# vers1_0.net
KiCad netlist of a schematic drawn in Altium Designer
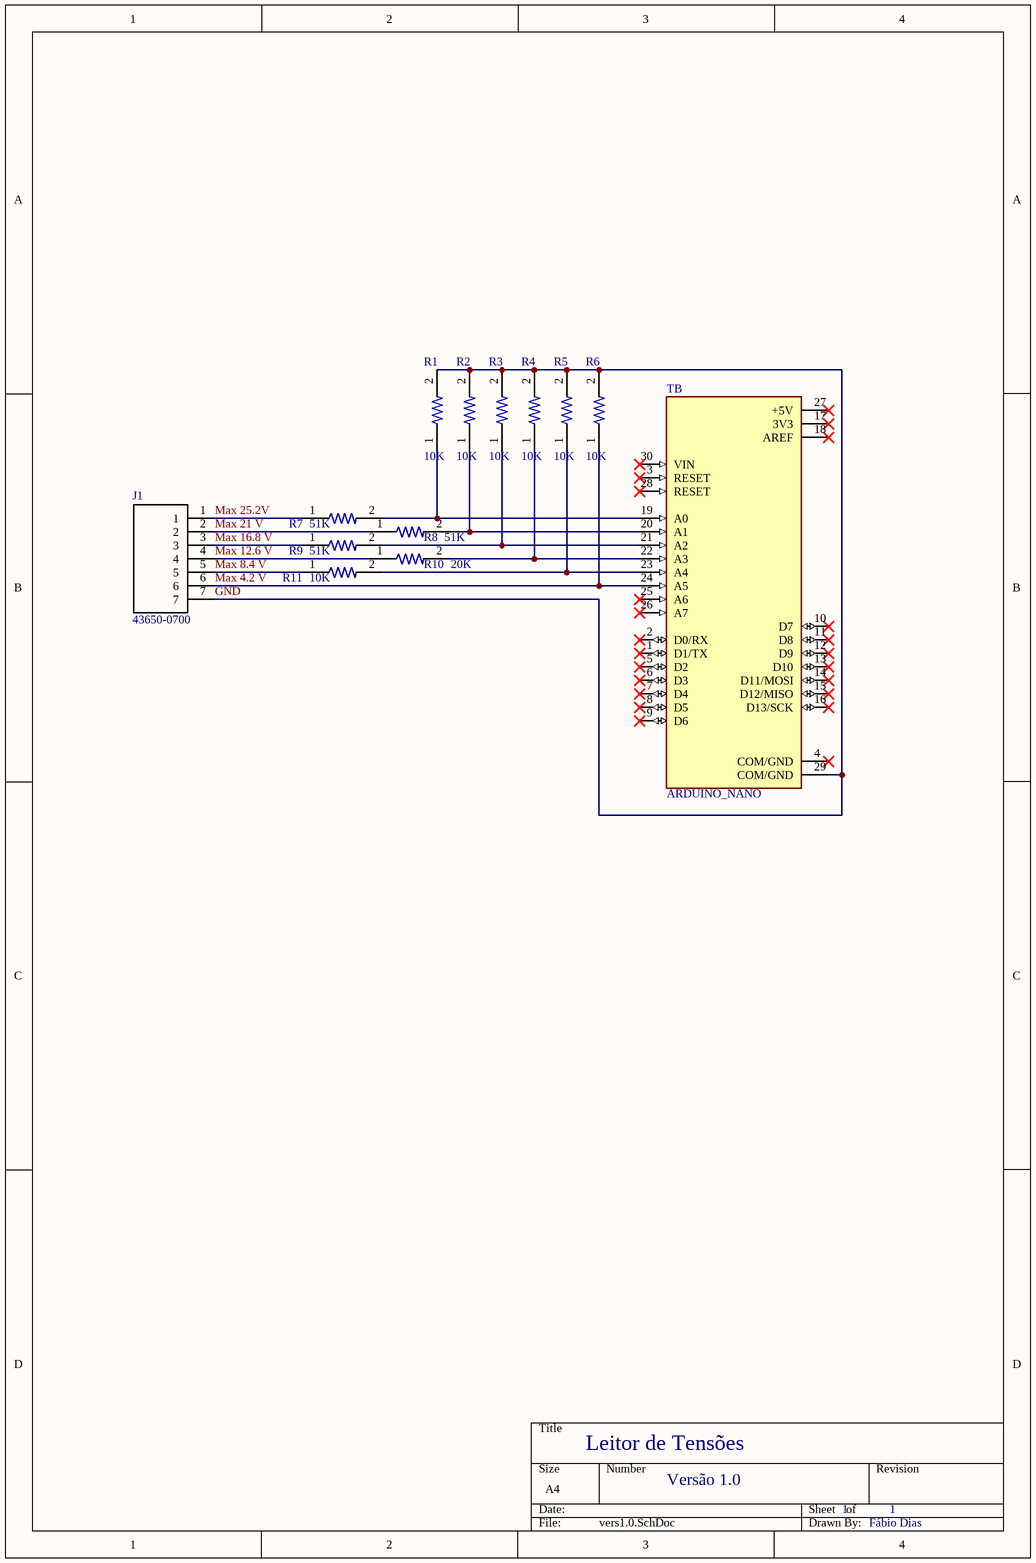
[diagram p0: vers1.0.SchDoc]

(export (version "E")
  (design (tool "Eeschema 10.0.6"))
  (components
    (comp (ref "J1")
      (value "43650-0700")
      (footprint "SamacSys:43650-07YY_R")
      (description "Connector")
      (fields (field (name "MOUSER PART NUMBER") "538-43650-0700"))
      (libsource (lib "*") (part "43650-0700"))
    )
    (comp (ref "R1")
      (value "10K")
      (footprint "R 0201")
      (description "Resistencia")
      (libsource (lib "MotoLibrary") (part "Resistencia"))
    )
    (comp (ref "R2")
      (value "10K")
      (footprint "R 0201")
      (description "Resistencia")
      (libsource (lib "MotoLibrary") (part "Resistencia"))
    )
    (comp (ref "R3")
      (value "10K")
      (footprint "R 0201")
      (description "Resistencia")
      (libsource (lib "MotoLibrary") (part "Resistencia"))
    )
    (comp (ref "R4")
      (value "10K")
      (footprint "R 0201")
      (description "Resistencia")
      (libsource (lib "MotoLibrary") (part "Resistencia"))
    )
    (comp (ref "R5")
      (value "10K")
      (footprint "R 0201")
      (description "Resistencia")
      (libsource (lib "MotoLibrary") (part "Resistencia"))
    )
    (comp (ref "R6")
      (value "10K")
      (footprint "R 0201")
      (description "Resistencia")
      (libsource (lib "MotoLibrary") (part "Resistencia"))
    )
    (comp (ref "R7")
      (value "51K")
      (footprint "R 0201")
      (description "Resistencia")
      (libsource (lib "MotoLibrary") (part "Resistencia"))
    )
    (comp (ref "R8")
      (value "51K")
      (footprint "R 0201")
      (description "Resistencia")
      (libsource (lib "MotoLibrary") (part "Resistencia"))
    )
    (comp (ref "R9")
      (value "51K")
      (footprint "R 0201")
      (description "Resistencia")
      (libsource (lib "MotoLibrary") (part "Resistencia"))
    )
    (comp (ref "R10")
      (value "20K")
      (footprint "R 0201")
      (description "Resistencia")
      (libsource (lib "MotoLibrary") (part "Resistencia"))
    )
    (comp (ref "R11")
      (value "10K")
      (footprint "R 0201")
      (description "Resistencia")
      (libsource (lib "MotoLibrary") (part "Resistencia"))
    )
    (comp (ref "TB")
      (value "ARDUINO_NANO")
      (footprint "SHIELD_ARDUINO_NANO")
      (description "ATSAMD21G18A Arduino Nano 33 IoT SAM D ARMÂ® CortexÂ®-M0+ MCU 32-Bit Embedded Evaluation Board")
      (fields (field (name "MP") "ARDUINO NANO") (field (name "MF") "Arduino"))
      (libsource (lib "ARDUINO_NANO") (part "ARDUINO_NANO"))
    )
  )
  (nets
    (net (code "1") (name "/GND") (class "Default")
      (node (ref "J1") (pin "7") (pinfunction "7_7") (pintype "passive"))
      (node (ref "R1") (pin "2") (pinfunction "2_2") (pintype "passive"))
      (node (ref "R2") (pin "2") (pinfunction "2_2") (pintype "passive"))
      (node (ref "R3") (pin "2") (pinfunction "2_2") (pintype "passive"))
      (node (ref "R4") (pin "2") (pinfunction "2_2") (pintype "passive"))
      (node (ref "R5") (pin "2") (pinfunction "2_2") (pintype "passive"))
      (node (ref "R6") (pin "2") (pinfunction "2_2") (pintype "passive"))
      (node (ref "TB") (pin "29") (pinfunction "COM/GND_29") (pintype "power_in"))
    )
    (net (code "2") (name "/Max 4.2 V") (class "Default")
      (node (ref "J1") (pin "6") (pinfunction "6_6") (pintype "passive"))
      (node (ref "R6") (pin "1") (pinfunction "1_1") (pintype "passive"))
      (node (ref "TB") (pin "24") (pinfunction "A5_24") (pintype "input"))
    )
    (net (code "3") (name "/Max 8.4 V") (class "Default")
      (node (ref "J1") (pin "5") (pinfunction "5_5") (pintype "passive"))
      (node (ref "R11") (pin "1") (pinfunction "1_1") (pintype "passive"))
    )
    (net (code "4") (name "/Max 12.6 V") (class "Default")
      (node (ref "J1") (pin "4") (pinfunction "4_4") (pintype "passive"))
      (node (ref "R10") (pin "1") (pinfunction "1_1") (pintype "passive"))
    )
    (net (code "5") (name "/Max 16.8 V") (class "Default")
      (node (ref "J1") (pin "3") (pinfunction "3_3") (pintype "passive"))
      (node (ref "R9") (pin "1") (pinfunction "1_1") (pintype "passive"))
    )
    (net (code "6") (name "/Max 21 V") (class "Default")
      (node (ref "J1") (pin "2") (pinfunction "2_2") (pintype "passive"))
      (node (ref "R8") (pin "1") (pinfunction "1_1") (pintype "passive"))
    )
    (net (code "7") (name "/Max 25.2V") (class "Default")
      (node (ref "J1") (pin "1") (pinfunction "1_1") (pintype "passive"))
      (node (ref "R7") (pin "1") (pinfunction "1_1") (pintype "passive"))
    )
    (net (code "8") (name "Net-(TB-A0)") (class "Default")
      (node (ref "R1") (pin "1") (pinfunction "1_1") (pintype "passive"))
      (node (ref "R7") (pin "2") (pinfunction "2_2") (pintype "passive"))
      (node (ref "TB") (pin "19") (pinfunction "A0_19") (pintype "input"))
    )
    (net (code "9") (name "Net-(TB-A1)") (class "Default")
      (node (ref "R2") (pin "1") (pinfunction "1_1") (pintype "passive"))
      (node (ref "R8") (pin "2") (pinfunction "2_2") (pintype "passive"))
      (node (ref "TB") (pin "20") (pinfunction "A1_20") (pintype "input"))
    )
    (net (code "10") (name "Net-(TB-A2)") (class "Default")
      (node (ref "R3") (pin "1") (pinfunction "1_1") (pintype "passive"))
      (node (ref "R9") (pin "2") (pinfunction "2_2") (pintype "passive"))
      (node (ref "TB") (pin "21") (pinfunction "A2_21") (pintype "input"))
    )
    (net (code "11") (name "Net-(TB-A3)") (class "Default")
      (node (ref "R10") (pin "2") (pinfunction "2_2") (pintype "passive"))
      (node (ref "R4") (pin "1") (pinfunction "1_1") (pintype "passive"))
      (node (ref "TB") (pin "22") (pinfunction "A3_22") (pintype "input"))
    )
    (net (code "12") (name "Net-(TB-A4)") (class "Default")
      (node (ref "R11") (pin "2") (pinfunction "2_2") (pintype "passive"))
      (node (ref "R5") (pin "1") (pinfunction "1_1") (pintype "passive"))
      (node (ref "TB") (pin "23") (pinfunction "A4_23") (pintype "input"))
    )
    (net (code "13") (name "unconnected-(TB-+5V-Pad27)") (class "Default")
      (node (ref "TB") (pin "27") (pinfunction "+5V_27") (pintype "power_in+no_connect"))
    )
    (net (code "14") (name "unconnected-(TB-3V3-Pad17)") (class "Default")
      (node (ref "TB") (pin "17") (pinfunction "3V3_17") (pintype "power_in+no_connect"))
    )
    (net (code "15") (name "unconnected-(TB-A6-Pad25)") (class "Default")
      (node (ref "TB") (pin "25") (pinfunction "A6_25") (pintype "input+no_connect"))
    )
    (net (code "16") (name "unconnected-(TB-A7-Pad26)") (class "Default")
      (node (ref "TB") (pin "26") (pinfunction "A7_26") (pintype "input+no_connect"))
    )
    (net (code "17") (name "unconnected-(TB-AREF-Pad18)") (class "Default")
      (node (ref "TB") (pin "18") (pinfunction "AREF_18") (pintype "power_in+no_connect"))
    )
    (net (code "18") (name "unconnected-(TB-COM{slash}GND-Pad4)") (class "Default")
      (node (ref "TB") (pin "4") (pinfunction "COM/GND_4") (pintype "power_in+no_connect"))
    )
    (net (code "19") (name "unconnected-(TB-D0{slash}RX-Pad2)") (class "Default")
      (node (ref "TB") (pin "2") (pinfunction "D0/RX_2") (pintype "bidirectional+no_connect"))
    )
    (net (code "20") (name "unconnected-(TB-D1{slash}TX-Pad1)") (class "Default")
      (node (ref "TB") (pin "1") (pinfunction "D1/TX_1") (pintype "bidirectional+no_connect"))
    )
    (net (code "21") (name "unconnected-(TB-D2-Pad5)") (class "Default")
      (node (ref "TB") (pin "5") (pinfunction "D2_5") (pintype "bidirectional+no_connect"))
    )
    (net (code "22") (name "unconnected-(TB-D3-Pad6)") (class "Default")
      (node (ref "TB") (pin "6") (pinfunction "D3_6") (pintype "bidirectional+no_connect"))
    )
    (net (code "23") (name "unconnected-(TB-D4-Pad7)") (class "Default")
      (node (ref "TB") (pin "7") (pinfunction "D4_7") (pintype "bidirectional+no_connect"))
    )
    (net (code "24") (name "unconnected-(TB-D5-Pad8)") (class "Default")
      (node (ref "TB") (pin "8") (pinfunction "D5_8") (pintype "bidirectional+no_connect"))
    )
    (net (code "25") (name "unconnected-(TB-D6-Pad9)") (class "Default")
      (node (ref "TB") (pin "9") (pinfunction "D6_9") (pintype "bidirectional+no_connect"))
    )
    (net (code "26") (name "unconnected-(TB-D7-Pad10)") (class "Default")
      (node (ref "TB") (pin "10") (pinfunction "D7_10") (pintype "bidirectional+no_connect"))
    )
    (net (code "27") (name "unconnected-(TB-D8-Pad11)") (class "Default")
      (node (ref "TB") (pin "11") (pinfunction "D8_11") (pintype "bidirectional+no_connect"))
    )
    (net (code "28") (name "unconnected-(TB-D9-Pad12)") (class "Default")
      (node (ref "TB") (pin "12") (pinfunction "D9_12") (pintype "bidirectional+no_connect"))
    )
    (net (code "29") (name "unconnected-(TB-D10-Pad13)") (class "Default")
      (node (ref "TB") (pin "13") (pinfunction "D10_13") (pintype "bidirectional+no_connect"))
    )
    (net (code "30") (name "unconnected-(TB-D11{slash}MOSI-Pad14)") (class "Default")
      (node (ref "TB") (pin "14") (pinfunction "D11/MOSI_14") (pintype "bidirectional+no_connect"))
    )
    (net (code "31") (name "unconnected-(TB-D12{slash}MISO-Pad15)") (class "Default")
      (node (ref "TB") (pin "15") (pinfunction "D12/MISO_15") (pintype "bidirectional+no_connect"))
    )
    (net (code "32") (name "unconnected-(TB-D13{slash}SCK-Pad16)") (class "Default")
      (node (ref "TB") (pin "16") (pinfunction "D13/SCK_16") (pintype "bidirectional+no_connect"))
    )
    (net (code "33") (name "unconnected-(TB-RESET-Pad3)") (class "Default")
      (node (ref "TB") (pin "3") (pinfunction "RESET_3") (pintype "input+no_connect"))
    )
    (net (code "34") (name "unconnected-(TB-RESET-Pad28)") (class "Default")
      (node (ref "TB") (pin "28") (pinfunction "RESET_28") (pintype "input+no_connect"))
    )
    (net (code "35") (name "unconnected-(TB-VIN-Pad30)") (class "Default")
      (node (ref "TB") (pin "30") (pinfunction "VIN_30") (pintype "input+no_connect"))
    )
  )
)
